# tester_breakout.net
KiCad netlist of a schematic drawn in Altium Designer
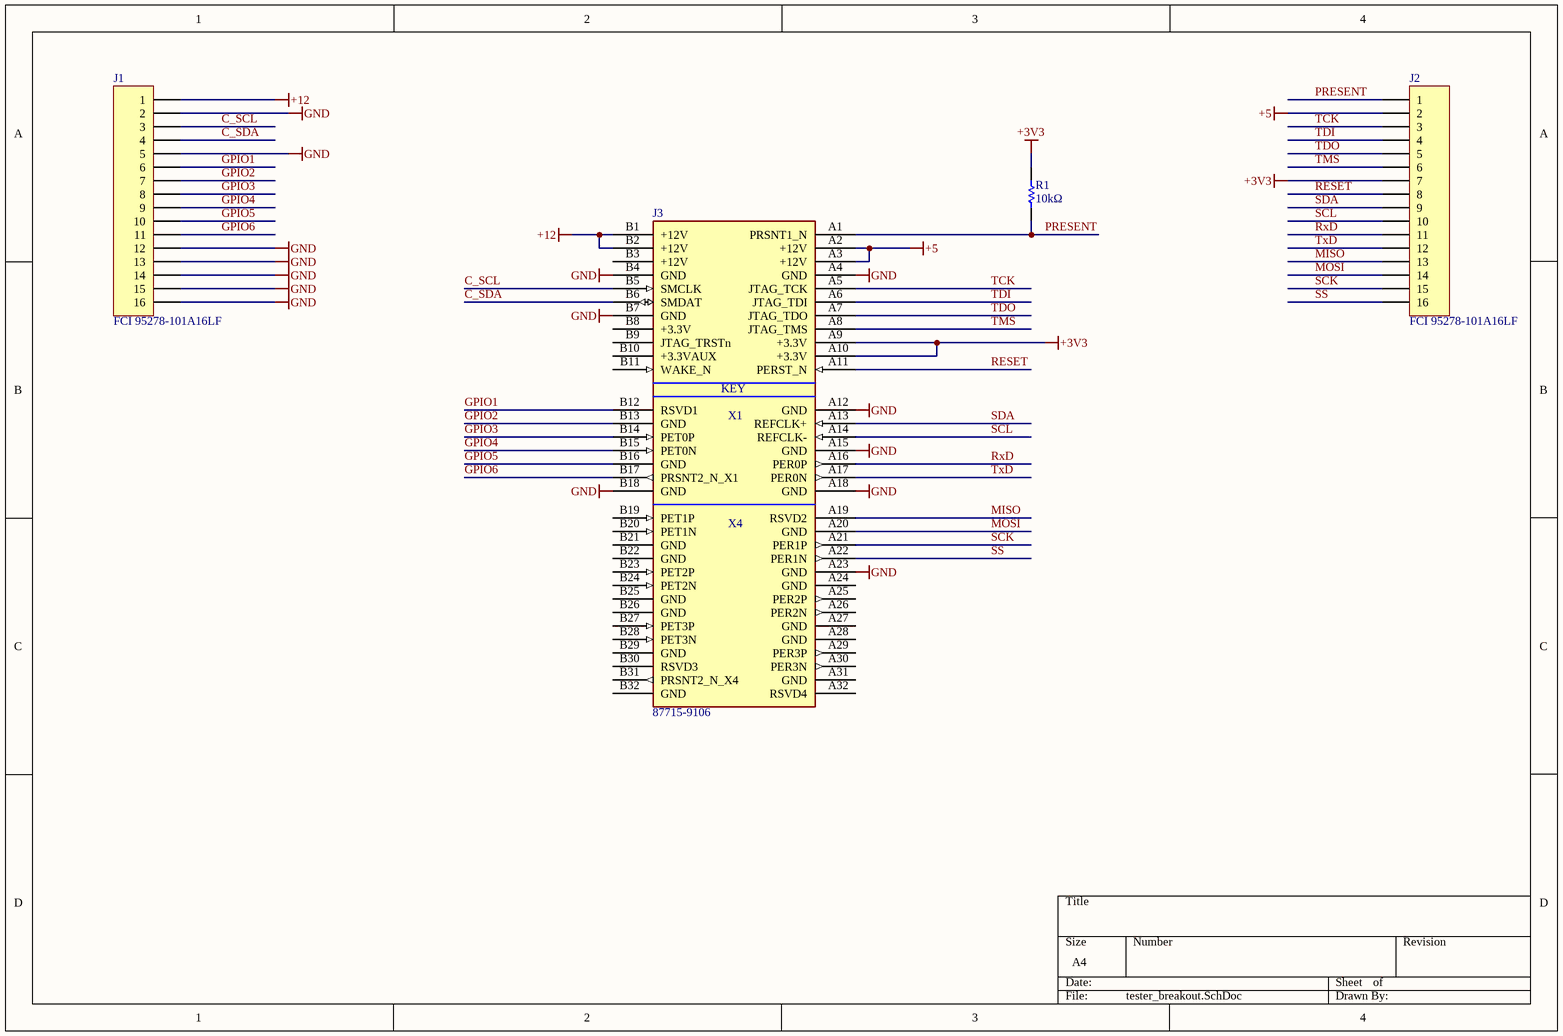
[diagram p0: tester_breakout.SchDoc]

(export (version "E")
  (design (tool "Eeschema 10.0.6"))
  (components
    (comp (ref "J1")
      (value "FCI 95278-101A16LF")
      (footprint "PCB-4a2gbb28wmnqwy5o1l64-1")
      (description "Wire-To-Board Connector, Ampmodu Mod Ii Series, Through Hole, Header, 16, 2.54 Mm")
      (libsource (lib "") (part "SYM-55f09e7f72328a37-2_1"))
    )
    (comp (ref "J2")
      (value "FCI 95278-101A16LF")
      (footprint "PCB-4a2gbb28wmnqwy5o1l64-1")
      (description "Wire-To-Board Connector, Ampmodu Mod Ii Series, Through Hole, Header, 16, 2.54 Mm")
      (libsource (lib "CommunityVault") (part "SYM-55f09e7f72328a37-2"))
    )
    (comp (ref "J3")
      (value "87715-9106")
      (footprint "PCB-jv25kdr3228vq428mjlt-1")
      (description "Conn PCI Express Card SKT 64 POS 2mm Solder ST Thru-Hole Tray")
      (libsource (lib "CommunityVault") (part "SYM-fe0c3608026a21cb-1"))
    )
    (comp (ref "R1")
      (value "RES-2")
      (footprint "PCB-a05eeaq2i5acw4uh0h7x-1")
      (description "Resistor; Thick Film; 10 Kilohms; 0.1 W; 1%; SMT; 0603; TCR 37 ppm/DegC; Tape and Reel")
      (fields (field (name "RESISTANCE") "10kΩ") (field (name "MANUFACTURER PART NUMBER") "CRCW060310K0FKEA"))
      (libsource (lib "CommunityVault") (part "CMP-4716668-21"))
    )
  )
  (nets
    (net (code "1") (name "+3V3") (class "Default")
      (node (ref "J2") (pin "7") (pinfunction "7_7") (pintype "passive"))
      (node (ref "J3") (pin "A10") (pinfunction "+3.3V_A10") (pintype "power_in"))
      (node (ref "J3") (pin "A9") (pinfunction "+3.3V_A9") (pintype "power_in"))
      (node (ref "R1") (pin "2") (pinfunction "2_2") (pintype "passive"))
    )
    (net (code "2") (name "+5") (class "Default")
      (node (ref "J2") (pin "2") (pinfunction "2_2") (pintype "passive"))
      (node (ref "J3") (pin "A2") (pinfunction "+12V_A2") (pintype "power_in"))
      (node (ref "J3") (pin "A3") (pinfunction "+12V_A3") (pintype "power_in"))
    )
    (net (code "3") (name "+12") (class "Default")
      (node (ref "J1") (pin "1") (pinfunction "1_1") (pintype "passive"))
      (node (ref "J3") (pin "B1") (pinfunction "+12V_B1") (pintype "power_in"))
      (node (ref "J3") (pin "B2") (pinfunction "+12V_B2") (pintype "power_in"))
    )
    (net (code "4") (name "/C_SCL") (class "Default")
      (node (ref "J1") (pin "3") (pinfunction "3_3") (pintype "passive"))
      (node (ref "J3") (pin "B5") (pinfunction "SMCLK_B5") (pintype "input"))
    )
    (net (code "5") (name "/C_SDA") (class "Default")
      (node (ref "J1") (pin "4") (pinfunction "4_4") (pintype "passive"))
      (node (ref "J3") (pin "B6") (pinfunction "SMDAT_B6") (pintype "bidirectional"))
    )
    (net (code "6") (name "/GPIO1") (class "Default")
      (node (ref "J1") (pin "6") (pinfunction "6_6") (pintype "passive"))
      (node (ref "J3") (pin "B12") (pinfunction "RSVD1_B12") (pintype "passive"))
    )
    (net (code "7") (name "/GPIO2") (class "Default")
      (node (ref "J1") (pin "7") (pinfunction "7_7") (pintype "passive"))
      (node (ref "J3") (pin "B13") (pinfunction "GND_B13") (pintype "power_in"))
    )
    (net (code "8") (name "/GPIO3") (class "Default")
      (node (ref "J1") (pin "8") (pinfunction "8_8") (pintype "passive"))
      (node (ref "J3") (pin "B14") (pinfunction "PET0P_B14") (pintype "input"))
    )
    (net (code "9") (name "/GPIO4") (class "Default")
      (node (ref "J1") (pin "9") (pinfunction "9_9") (pintype "passive"))
      (node (ref "J3") (pin "B15") (pinfunction "PET0N_B15") (pintype "input"))
    )
    (net (code "10") (name "/GPIO5") (class "Default")
      (node (ref "J1") (pin "10") (pinfunction "10_10") (pintype "passive"))
      (node (ref "J3") (pin "B16") (pinfunction "GND_B16") (pintype "power_in"))
    )
    (net (code "11") (name "/GPIO6") (class "Default")
      (node (ref "J1") (pin "11") (pinfunction "11_11") (pintype "passive"))
      (node (ref "J3") (pin "B17") (pinfunction "PRSNT2_N_X1_B17") (pintype "output"))
    )
    (net (code "12") (name "/MISO") (class "Default")
      (node (ref "J2") (pin "13") (pinfunction "13_13") (pintype "passive"))
      (node (ref "J3") (pin "A19") (pinfunction "RSVD2_A19") (pintype "passive"))
    )
    (net (code "13") (name "/MOSI") (class "Default")
      (node (ref "J2") (pin "14") (pinfunction "14_14") (pintype "passive"))
      (node (ref "J3") (pin "A20") (pinfunction "GND_A20") (pintype "power_in"))
    )
    (net (code "14") (name "/PRESENT") (class "Default")
      (node (ref "J2") (pin "1") (pinfunction "1_1") (pintype "passive"))
      (node (ref "J3") (pin "A1") (pinfunction "PRSNT1_N_A1") (pintype "passive"))
      (node (ref "R1") (pin "1") (pinfunction "1_1") (pintype "passive"))
    )
    (net (code "15") (name "/RESET") (class "Default")
      (node (ref "J2") (pin "8") (pinfunction "8_8") (pintype "passive"))
      (node (ref "J3") (pin "A11") (pinfunction "PERST_N_A11") (pintype "input"))
    )
    (net (code "16") (name "/RxD") (class "Default")
      (node (ref "J2") (pin "11") (pinfunction "11_11") (pintype "passive"))
      (node (ref "J3") (pin "A16") (pinfunction "PER0P_A16") (pintype "output"))
    )
    (net (code "17") (name "/SCK") (class "Default")
      (node (ref "J2") (pin "15") (pinfunction "15_15") (pintype "passive"))
      (node (ref "J3") (pin "A21") (pinfunction "PER1P_A21") (pintype "output"))
    )
    (net (code "18") (name "/SCL") (class "Default")
      (node (ref "J2") (pin "10") (pinfunction "10_10") (pintype "passive"))
      (node (ref "J3") (pin "A14") (pinfunction "REFCLK-_A14") (pintype "input"))
    )
    (net (code "19") (name "/SDA") (class "Default")
      (node (ref "J2") (pin "9") (pinfunction "9_9") (pintype "passive"))
      (node (ref "J3") (pin "A13") (pinfunction "REFCLK+_A13") (pintype "input"))
    )
    (net (code "20") (name "/SS") (class "Default")
      (node (ref "J2") (pin "16") (pinfunction "16_16") (pintype "passive"))
      (node (ref "J3") (pin "A22") (pinfunction "PER1N_A22") (pintype "output"))
    )
    (net (code "21") (name "/TCK") (class "Default")
      (node (ref "J2") (pin "3") (pinfunction "3_3") (pintype "passive"))
      (node (ref "J3") (pin "A5") (pinfunction "JTAG_TCK_A5") (pintype "passive"))
    )
    (net (code "22") (name "/TDI") (class "Default")
      (node (ref "J2") (pin "4") (pinfunction "4_4") (pintype "passive"))
      (node (ref "J3") (pin "A6") (pinfunction "JTAG_TDI_A6") (pintype "passive"))
    )
    (net (code "23") (name "/TDO") (class "Default")
      (node (ref "J2") (pin "5") (pinfunction "5_5") (pintype "passive"))
      (node (ref "J3") (pin "A7") (pinfunction "JTAG_TDO_A7") (pintype "passive"))
    )
    (net (code "24") (name "/TMS") (class "Default")
      (node (ref "J2") (pin "6") (pinfunction "6_6") (pintype "passive"))
      (node (ref "J3") (pin "A8") (pinfunction "JTAG_TMS_A8") (pintype "passive"))
    )
    (net (code "25") (name "/TxD") (class "Default")
      (node (ref "J2") (pin "12") (pinfunction "12_12") (pintype "passive"))
      (node (ref "J3") (pin "A17") (pinfunction "PER0N_A17") (pintype "output"))
    )
    (net (code "26") (name "GND") (class "Default")
      (node (ref "J1") (pin "12") (pinfunction "12_12") (pintype "passive"))
      (node (ref "J1") (pin "13") (pinfunction "13_13") (pintype "passive"))
      (node (ref "J1") (pin "14") (pinfunction "14_14") (pintype "passive"))
      (node (ref "J1") (pin "15") (pinfunction "15_15") (pintype "passive"))
      (node (ref "J1") (pin "16") (pinfunction "16_16") (pintype "passive"))
      (node (ref "J1") (pin "2") (pinfunction "2_2") (pintype "passive"))
      (node (ref "J1") (pin "5") (pinfunction "5_5") (pintype "passive"))
      (node (ref "J3") (pin "A12") (pinfunction "GND_A12") (pintype "power_in"))
      (node (ref "J3") (pin "A15") (pinfunction "GND_A15") (pintype "power_in"))
      (node (ref "J3") (pin "A18") (pinfunction "GND_A18") (pintype "power_in"))
      (node (ref "J3") (pin "A23") (pinfunction "GND_A23") (pintype "power_in"))
      (node (ref "J3") (pin "A4") (pinfunction "GND_A4") (pintype "power_in"))
      (node (ref "J3") (pin "B18") (pinfunction "GND_B18") (pintype "power_in"))
      (node (ref "J3") (pin "B4") (pinfunction "GND_B4") (pintype "power_in"))
      (node (ref "J3") (pin "B7") (pinfunction "GND_B7") (pintype "power_in"))
    )
    (net (code "27") (name "unconnected-(J3-+3.3V-PadB8)") (class "Default")
      (node (ref "J3") (pin "B8") (pinfunction "+3.3V_B8") (pintype "power_in"))
    )
    (net (code "28") (name "unconnected-(J3-+3.3VAUX-PadB10)") (class "Default")
      (node (ref "J3") (pin "B10") (pinfunction "+3.3VAUX_B10") (pintype "power_in"))
    )
    (net (code "29") (name "unconnected-(J3-+12V-PadB3)") (class "Default")
      (node (ref "J3") (pin "B3") (pinfunction "+12V_B3") (pintype "power_in"))
    )
    (net (code "30") (name "unconnected-(J3-GND-PadA24)") (class "Default")
      (node (ref "J3") (pin "A24") (pinfunction "GND_A24") (pintype "power_in"))
    )
    (net (code "31") (name "unconnected-(J3-GND-PadA27)") (class "Default")
      (node (ref "J3") (pin "A27") (pinfunction "GND_A27") (pintype "power_in"))
    )
    (net (code "32") (name "unconnected-(J3-GND-PadA28)") (class "Default")
      (node (ref "J3") (pin "A28") (pinfunction "GND_A28") (pintype "power_in"))
    )
    (net (code "33") (name "unconnected-(J3-GND-PadA31)") (class "Default")
      (node (ref "J3") (pin "A31") (pinfunction "GND_A31") (pintype "power_in"))
    )
    (net (code "34") (name "unconnected-(J3-GND-PadB21)") (class "Default")
      (node (ref "J3") (pin "B21") (pinfunction "GND_B21") (pintype "power_in"))
    )
    (net (code "35") (name "unconnected-(J3-GND-PadB22)") (class "Default")
      (node (ref "J3") (pin "B22") (pinfunction "GND_B22") (pintype "power_in"))
    )
    (net (code "36") (name "unconnected-(J3-GND-PadB25)") (class "Default")
      (node (ref "J3") (pin "B25") (pinfunction "GND_B25") (pintype "power_in"))
    )
    (net (code "37") (name "unconnected-(J3-GND-PadB26)") (class "Default")
      (node (ref "J3") (pin "B26") (pinfunction "GND_B26") (pintype "power_in"))
    )
    (net (code "38") (name "unconnected-(J3-GND-PadB29)") (class "Default")
      (node (ref "J3") (pin "B29") (pinfunction "GND_B29") (pintype "power_in"))
    )
    (net (code "39") (name "unconnected-(J3-GND-PadB32)") (class "Default")
      (node (ref "J3") (pin "B32") (pinfunction "GND_B32") (pintype "power_in"))
    )
    (net (code "40") (name "unconnected-(J3-JTAG_TRSTn-PadB9)") (class "Default")
      (node (ref "J3") (pin "B9") (pinfunction "JTAG_TRSTn_B9") (pintype "passive"))
    )
    (net (code "41") (name "unconnected-(J3-PER2N-PadA26)") (class "Default")
      (node (ref "J3") (pin "A26") (pinfunction "PER2N_A26") (pintype "output"))
    )
    (net (code "42") (name "unconnected-(J3-PER2P-PadA25)") (class "Default")
      (node (ref "J3") (pin "A25") (pinfunction "PER2P_A25") (pintype "output"))
    )
    (net (code "43") (name "unconnected-(J3-PER3N-PadA30)") (class "Default")
      (node (ref "J3") (pin "A30") (pinfunction "PER3N_A30") (pintype "output"))
    )
    (net (code "44") (name "unconnected-(J3-PER3P-PadA29)") (class "Default")
      (node (ref "J3") (pin "A29") (pinfunction "PER3P_A29") (pintype "output"))
    )
    (net (code "45") (name "unconnected-(J3-PET1N-PadB20)") (class "Default")
      (node (ref "J3") (pin "B20") (pinfunction "PET1N_B20") (pintype "input"))
    )
    (net (code "46") (name "unconnected-(J3-PET1P-PadB19)") (class "Default")
      (node (ref "J3") (pin "B19") (pinfunction "PET1P_B19") (pintype "input"))
    )
    (net (code "47") (name "unconnected-(J3-PET2N-PadB24)") (class "Default")
      (node (ref "J3") (pin "B24") (pinfunction "PET2N_B24") (pintype "input"))
    )
    (net (code "48") (name "unconnected-(J3-PET2P-PadB23)") (class "Default")
      (node (ref "J3") (pin "B23") (pinfunction "PET2P_B23") (pintype "input"))
    )
    (net (code "49") (name "unconnected-(J3-PET3N-PadB28)") (class "Default")
      (node (ref "J3") (pin "B28") (pinfunction "PET3N_B28") (pintype "input"))
    )
    (net (code "50") (name "unconnected-(J3-PET3P-PadB27)") (class "Default")
      (node (ref "J3") (pin "B27") (pinfunction "PET3P_B27") (pintype "input"))
    )
    (net (code "51") (name "unconnected-(J3-PRSNT2_N_X4-PadB31)") (class "Default")
      (node (ref "J3") (pin "B31") (pinfunction "PRSNT2_N_X4_B31") (pintype "output"))
    )
    (net (code "52") (name "unconnected-(J3-RSVD3-PadB30)") (class "Default")
      (node (ref "J3") (pin "B30") (pinfunction "RSVD3_B30") (pintype "passive"))
    )
    (net (code "53") (name "unconnected-(J3-RSVD4-PadA32)") (class "Default")
      (node (ref "J3") (pin "A32") (pinfunction "RSVD4_A32") (pintype "passive"))
    )
    (net (code "54") (name "unconnected-(J3-WAKE_N-PadB11)") (class "Default")
      (node (ref "J3") (pin "B11") (pinfunction "WAKE_N_B11") (pintype "input"))
    )
  )
)
